# Ring_opto_interface_v3.net
KiCad netlist of a schematic drawn in EAGLE
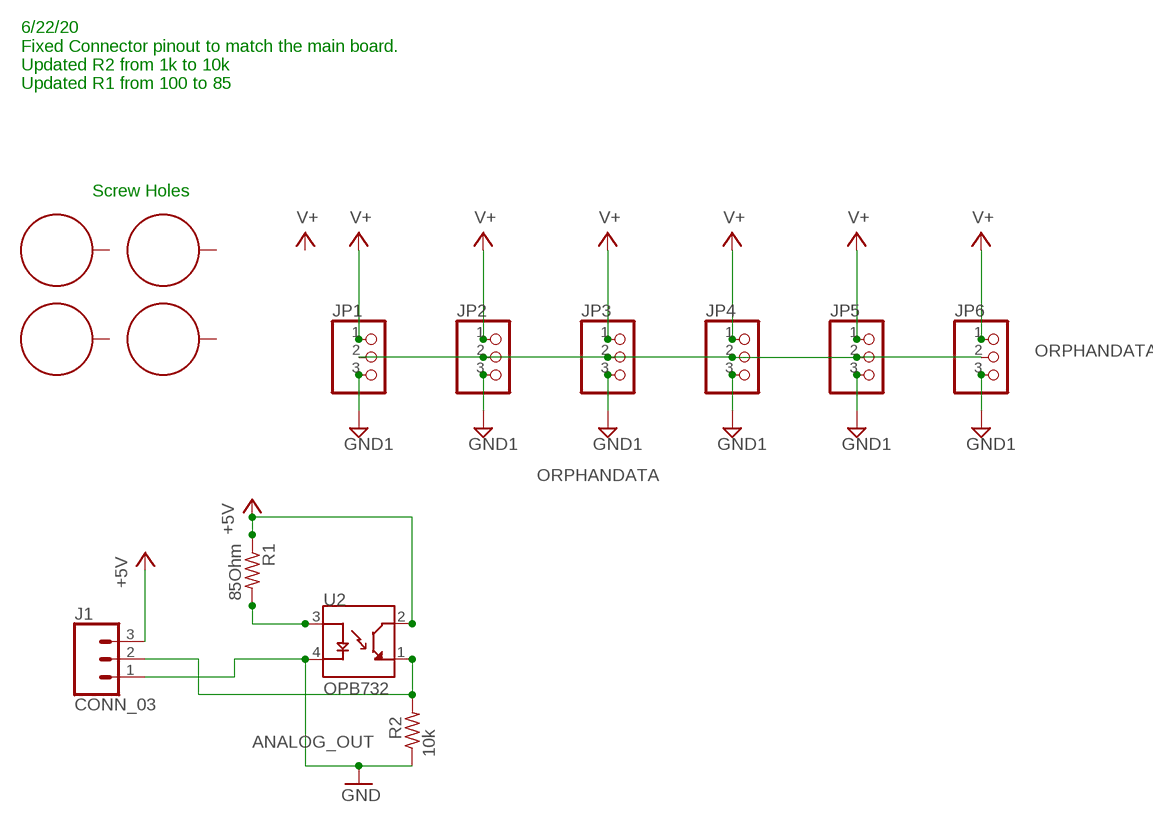
[diagram p0: schematic, sheet 1]

(export (version "E")
  (design (tool "Eeschema 10.0.6"))
  (components
    (comp (ref "H1")
      (value "STANDOFF_ELECTRICAL5-32")
      (footprint "eagle-import:STANDOFF_ELECTRICAL_5_32")
      (libsource (lib "eagle-import") (part "STANDOFF_ELECTRICAL5-32"))
    )
    (comp (ref "H2")
      (value "STANDOFF_ELECTRICAL5-32")
      (footprint "eagle-import:STANDOFF_ELECTRICAL_5_32")
      (libsource (lib "eagle-import") (part "STANDOFF_ELECTRICAL5-32"))
    )
    (comp (ref "H3")
      (value "STANDOFF_ELECTRICAL5-32")
      (footprint "eagle-import:STANDOFF_ELECTRICAL_5_32")
      (libsource (lib "eagle-import") (part "STANDOFF_ELECTRICAL5-32"))
    )
    (comp (ref "H4")
      (value "STANDOFF_ELECTRICAL5-32")
      (footprint "eagle-import:STANDOFF_ELECTRICAL_5_32")
      (libsource (lib "eagle-import") (part "STANDOFF_ELECTRICAL5-32"))
    )
    (comp (ref "J1")
      (value "CONN_03")
      (footprint "eagle-import:1X03_3.5MM_RA")
      (libsource (lib "eagle-import") (part "CONN_03"))
    )
    (comp (ref "JP1")
      (value "PINHD-1X3CB")
      (footprint "eagle-import:1X03-CLEANBIG")
      (libsource (lib "eagle-import") (part "PINHD-1X3CB"))
    )
    (comp (ref "JP2")
      (value "PINHD-1X3CB")
      (footprint "eagle-import:1X03-CLEANBIG")
      (libsource (lib "eagle-import") (part "PINHD-1X3CB"))
    )
    (comp (ref "JP3")
      (value "PINHD-1X3CB")
      (footprint "eagle-import:1X03-CLEANBIG")
      (libsource (lib "eagle-import") (part "PINHD-1X3CB"))
    )
    (comp (ref "JP4")
      (value "PINHD-1X3CB")
      (footprint "eagle-import:1X03-CLEANBIG")
      (libsource (lib "eagle-import") (part "PINHD-1X3CB"))
    )
    (comp (ref "JP5")
      (value "PINHD-1X3CB")
      (footprint "eagle-import:1X03-CLEANBIG")
      (libsource (lib "eagle-import") (part "PINHD-1X3CB"))
    )
    (comp (ref "JP6")
      (value "PINHD-1X3CB")
      (footprint "eagle-import:1X03-CLEANBIG")
      (libsource (lib "eagle-import") (part "PINHD-1X3CB"))
    )
    (comp (ref "R1")
      (value "85Ohm")
      (footprint "eagle-import:RESAD1176W63L850D250B")
      (libsource (lib "eagle-import") (part "R-USAXIAL-11.7MM-PITCH_"))
    )
    (comp (ref "R2")
      (value "10k")
      (footprint "eagle-import:RESAD1176W63L850D250B")
      (libsource (lib "eagle-import") (part "R-USAXIAL-11.7MM-PITCH_"))
    )
    (comp (ref "U2")
      (value "OPB732")
      (footprint "eagle-import:OPTO_OPB732")
      (fields (field (name "MF") "TT Electronics/Optek"))
      (libsource (lib "eagle-import") (part "OPB732"))
    )
  )
  (nets
    (net (code "1") (name "+5V") (class "Default")
      (node (ref "J1") (pin "3") (pinfunction "3_3") (pintype "passive"))
      (node (ref "R1") (pin "1") (pinfunction "1_1") (pintype "passive"))
      (node (ref "U2") (pin "2") (pinfunction "CT_2") (pintype "passive"))
    )
    (net (code "2") (name "/ANALOG_OUT") (class "Default")
      (node (ref "J1") (pin "2") (pinfunction "2_2") (pintype "passive"))
      (node (ref "R2") (pin "2") (pinfunction "2_2") (pintype "passive"))
      (node (ref "U2") (pin "1") (pinfunction "ET_1") (pintype "passive"))
    )
    (net (code "3") (name "/ORPHANDATA") (class "Default")
      (node (ref "JP1") (pin "2") (pinfunction "2_2") (pintype "passive"))
      (node (ref "JP2") (pin "2") (pinfunction "2_2") (pintype "passive"))
      (node (ref "JP3") (pin "2") (pinfunction "2_2") (pintype "passive"))
      (node (ref "JP4") (pin "2") (pinfunction "2_2") (pintype "passive"))
      (node (ref "JP5") (pin "2") (pinfunction "2_2") (pintype "passive"))
      (node (ref "JP6") (pin "2") (pinfunction "2_2") (pintype "passive"))
    )
    (net (code "4") (name "GND") (class "Default")
      (node (ref "J1") (pin "1") (pinfunction "1_1") (pintype "passive"))
      (node (ref "R2") (pin "1") (pinfunction "1_1") (pintype "passive"))
      (node (ref "U2") (pin "4") (pinfunction "C_4") (pintype "passive"))
    )
    (net (code "5") (name "GND1") (class "Default")
      (node (ref "JP1") (pin "3") (pinfunction "3_3") (pintype "passive"))
      (node (ref "JP2") (pin "3") (pinfunction "3_3") (pintype "passive"))
      (node (ref "JP3") (pin "3") (pinfunction "3_3") (pintype "passive"))
      (node (ref "JP4") (pin "3") (pinfunction "3_3") (pintype "passive"))
      (node (ref "JP5") (pin "3") (pinfunction "3_3") (pintype "passive"))
      (node (ref "JP6") (pin "3") (pinfunction "3_3") (pintype "passive"))
    )
    (net (code "6") (name "Net-(U2-A)") (class "Default")
      (node (ref "R1") (pin "2") (pinfunction "2_2") (pintype "passive"))
      (node (ref "U2") (pin "3") (pinfunction "A_3") (pintype "passive"))
    )
    (net (code "7") (name "V+") (class "Default")
      (node (ref "JP1") (pin "1") (pinfunction "1_1") (pintype "passive"))
      (node (ref "JP2") (pin "1") (pinfunction "1_1") (pintype "passive"))
      (node (ref "JP3") (pin "1") (pinfunction "1_1") (pintype "passive"))
      (node (ref "JP4") (pin "1") (pinfunction "1_1") (pintype "passive"))
      (node (ref "JP5") (pin "1") (pinfunction "1_1") (pintype "passive"))
      (node (ref "JP6") (pin "1") (pinfunction "1_1") (pintype "passive"))
    )
    (net (code "8") (name "unconnected-(H1-P$1-PadP1)") (class "Default")
      (node (ref "H1") (pin "P1") (pinfunction "P$1_P1") (pintype "bidirectional"))
    )
    (net (code "9") (name "unconnected-(H2-P$1-PadP1)") (class "Default")
      (node (ref "H2") (pin "P1") (pinfunction "P$1_P1") (pintype "bidirectional"))
    )
    (net (code "10") (name "unconnected-(H3-P$1-PadP1)") (class "Default")
      (node (ref "H3") (pin "P1") (pinfunction "P$1_P1") (pintype "bidirectional"))
    )
    (net (code "11") (name "unconnected-(H4-P$1-PadP1)") (class "Default")
      (node (ref "H4") (pin "P1") (pinfunction "P$1_P1") (pintype "bidirectional"))
    )
  )
)
